# VM3300_V0_1.net
KiCad netlist of a schematic drawn in Altium Designer
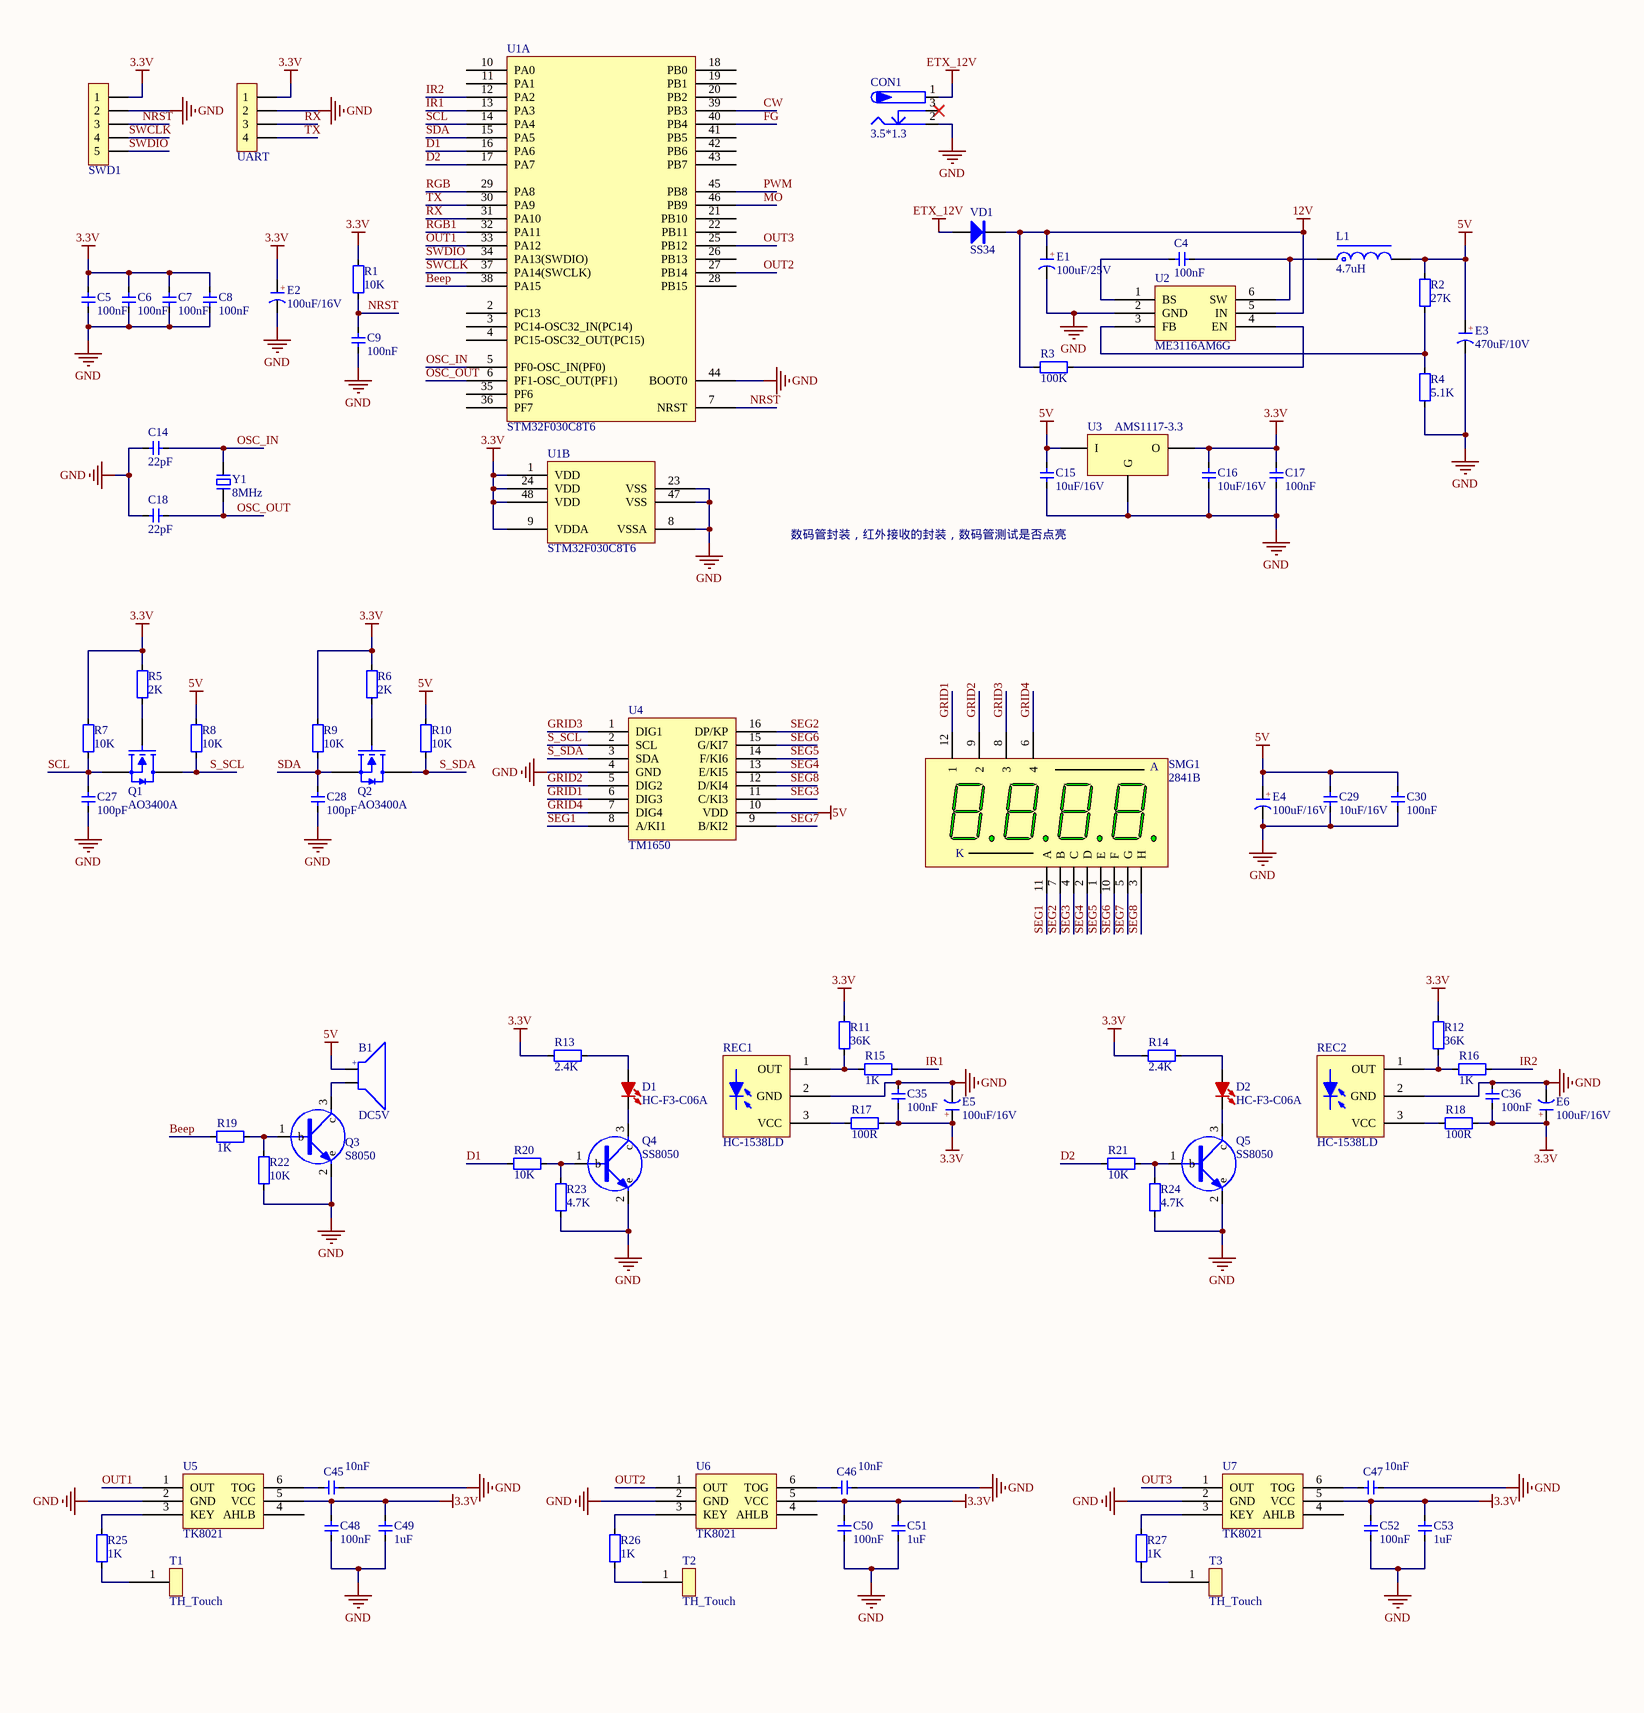
[diagram p0: VM3300_V0.1.SchDoc, left]
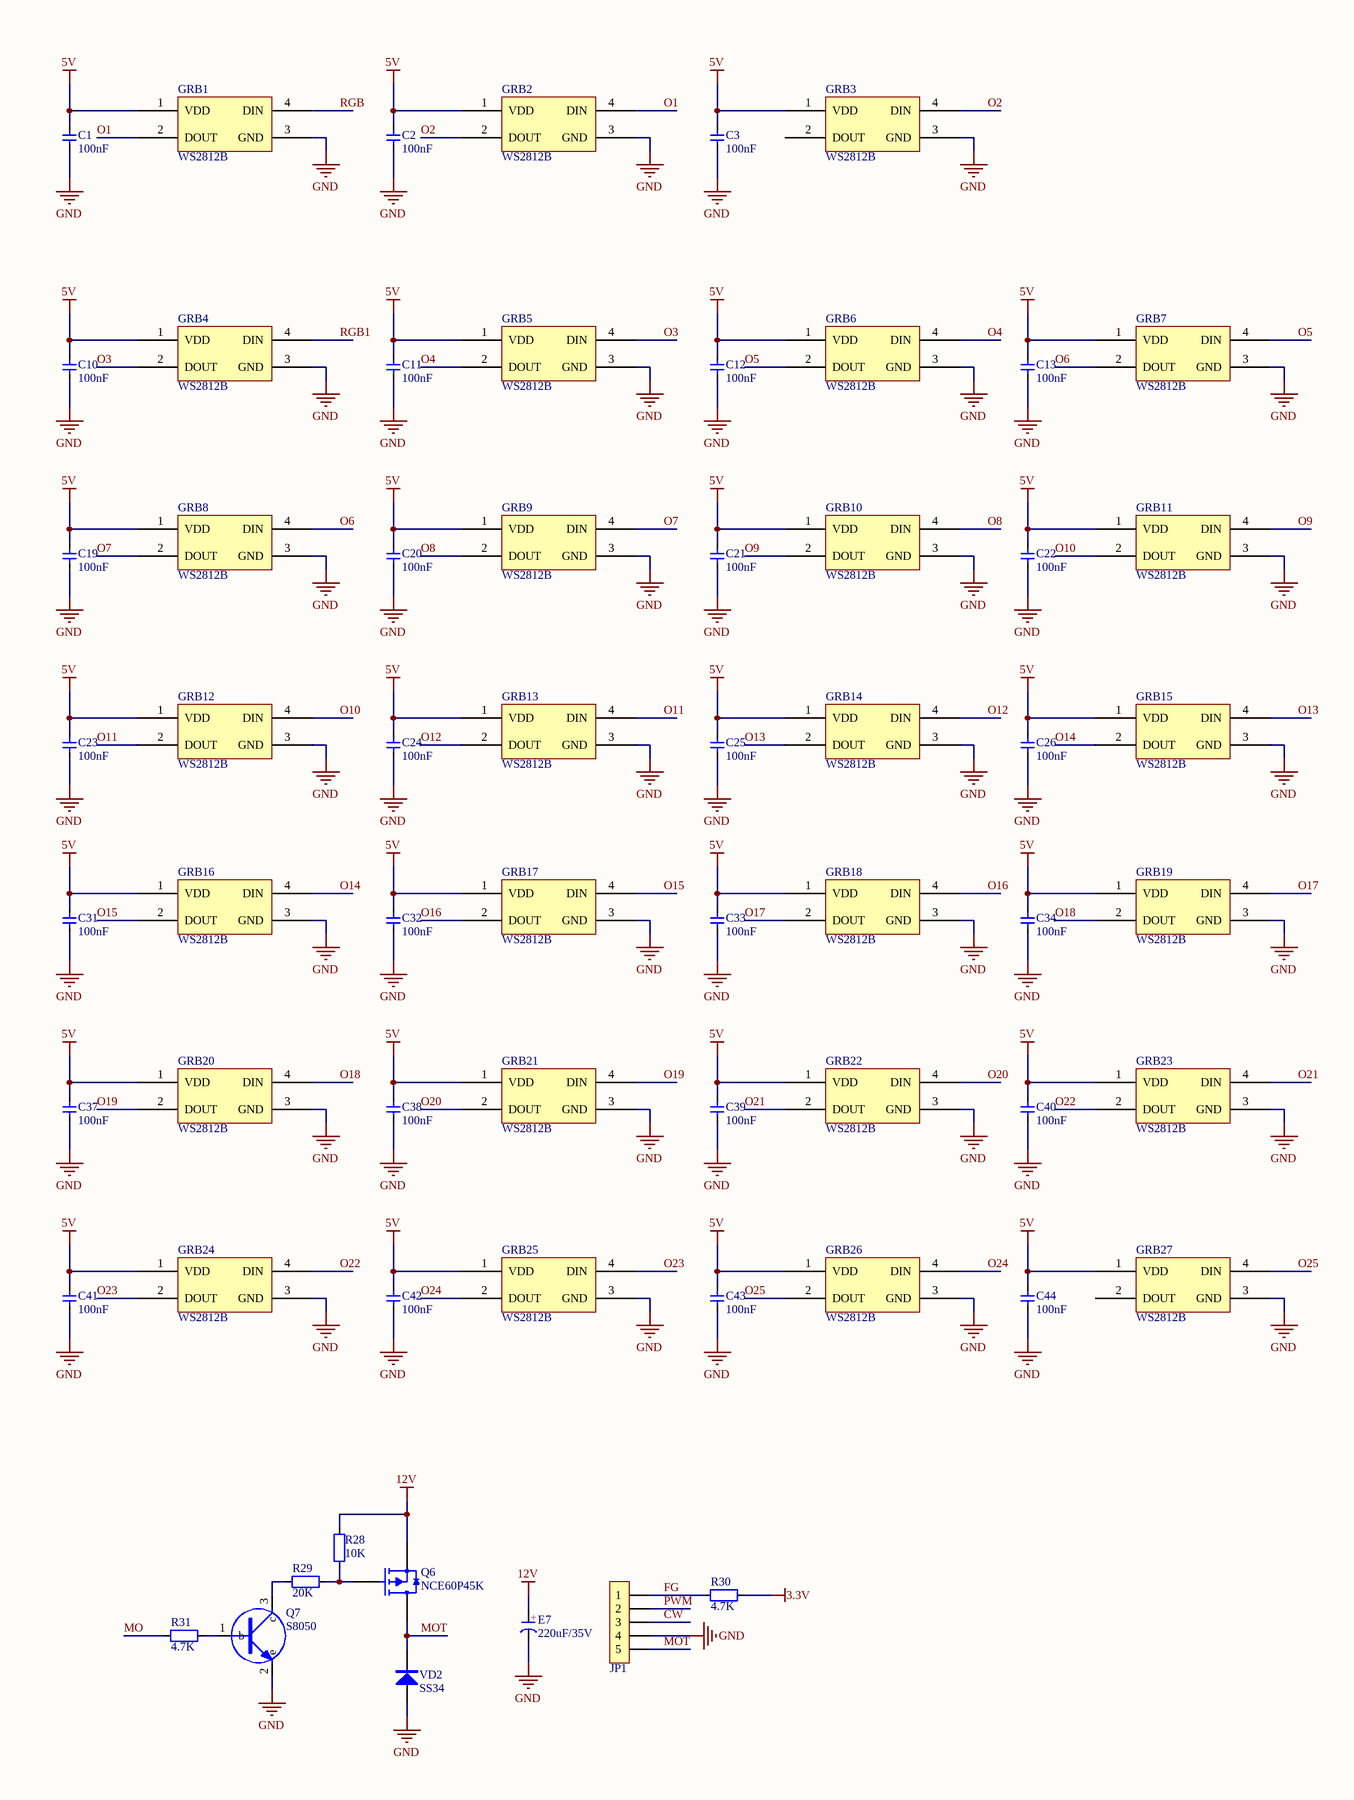
[diagram p1: VM3300_V0.1.SchDoc, right]

(export (version "E")
  (design (tool "Eeschema 10.0.6"))
  (components
    (comp (ref "B1")
      (value "DC5V")
      (footprint "BEEP 7.6x12x7.5")
      (description "蜂鸣器")
      (fields (field (name "版权归属") "源创客"))
      (libsource (lib "模块器件") (part "BEEP"))
    )
    (comp (ref "C1")
      (value "100nF")
      (footprint "C 0603")
      (description "无极性贴片电容")
      (fields (field (name "版权归属") "源创客"))
      (libsource (lib "电容") (part "C"))
    )
    (comp (ref "C2")
      (value "100nF")
      (footprint "C 0603")
      (description "无极性贴片电容")
      (fields (field (name "版权归属") "源创客"))
      (libsource (lib "电容") (part "C"))
    )
    (comp (ref "C3")
      (value "100nF")
      (footprint "C 0603")
      (description "无极性贴片电容")
      (fields (field (name "版权归属") "源创客"))
      (libsource (lib "电容") (part "C"))
    )
    (comp (ref "C4")
      (value "100nF")
      (footprint "C 0603")
      (description "无极性贴片电容")
      (fields (field (name "版权归属") "源创客"))
      (libsource (lib "电容") (part "C"))
    )
    (comp (ref "C5")
      (value "100nF")
      (footprint "C 0603")
      (description "无极性贴片电容")
      (fields (field (name "版权归属") "源创客"))
      (libsource (lib "电容") (part "C"))
    )
    (comp (ref "C6")
      (value "100nF")
      (footprint "C 0603")
      (description "无极性贴片电容")
      (fields (field (name "版权归属") "源创客"))
      (libsource (lib "电容") (part "C"))
    )
    (comp (ref "C7")
      (value "100nF")
      (footprint "C 0603")
      (description "无极性贴片电容")
      (fields (field (name "版权归属") "源创客"))
      (libsource (lib "电容") (part "C"))
    )
    (comp (ref "C8")
      (value "100nF")
      (footprint "C 0603")
      (description "无极性贴片电容")
      (fields (field (name "版权归属") "源创客"))
      (libsource (lib "电容") (part "C"))
    )
    (comp (ref "C9")
      (value "100nF")
      (footprint "C 0603")
      (description "无极性贴片电容")
      (fields (field (name "版权归属") "源创客"))
      (libsource (lib "电容") (part "C"))
    )
    (comp (ref "C10")
      (value "100nF")
      (footprint "C 0603")
      (description "无极性贴片电容")
      (fields (field (name "版权归属") "源创客"))
      (libsource (lib "电容") (part "C"))
    )
    (comp (ref "C11")
      (value "100nF")
      (footprint "C 0603")
      (description "无极性贴片电容")
      (fields (field (name "版权归属") "源创客"))
      (libsource (lib "电容") (part "C"))
    )
    (comp (ref "C12")
      (value "100nF")
      (footprint "C 0603")
      (description "无极性贴片电容")
      (fields (field (name "版权归属") "源创客"))
      (libsource (lib "电容") (part "C"))
    )
    (comp (ref "C13")
      (value "100nF")
      (footprint "C 0603")
      (description "无极性贴片电容")
      (fields (field (name "版权归属") "源创客"))
      (libsource (lib "电容") (part "C"))
    )
    (comp (ref "C14")
      (value "22pF")
      (footprint "C 0603")
      (description "无极性贴片电容")
      (fields (field (name "版权归属") "源创客"))
      (libsource (lib "电容") (part "C"))
    )
    (comp (ref "C15")
      (value "10uF/16V")
      (footprint "C 0805")
      (description "无极性贴片电容")
      (fields (field (name "版权归属") "源创客"))
      (libsource (lib "电容") (part "C"))
    )
    (comp (ref "C16")
      (value "10uF/16V")
      (footprint "C 0805")
      (description "无极性贴片电容")
      (fields (field (name "版权归属") "源创客"))
      (libsource (lib "电容") (part "C"))
    )
    (comp (ref "C17")
      (value "100nF")
      (footprint "C 0603")
      (description "无极性贴片电容")
      (fields (field (name "版权归属") "源创客"))
      (libsource (lib "电容") (part "C"))
    )
    (comp (ref "C18")
      (value "22pF")
      (footprint "C 0603")
      (description "无极性贴片电容")
      (fields (field (name "版权归属") "源创客"))
      (libsource (lib "电容") (part "C"))
    )
    (comp (ref "C19")
      (value "100nF")
      (footprint "C 0603")
      (description "无极性贴片电容")
      (fields (field (name "版权归属") "源创客"))
      (libsource (lib "电容") (part "C"))
    )
    (comp (ref "C20")
      (value "100nF")
      (footprint "C 0603")
      (description "无极性贴片电容")
      (fields (field (name "版权归属") "源创客"))
      (libsource (lib "电容") (part "C"))
    )
    (comp (ref "C21")
      (value "100nF")
      (footprint "C 0603")
      (description "无极性贴片电容")
      (fields (field (name "版权归属") "源创客"))
      (libsource (lib "电容") (part "C"))
    )
    (comp (ref "C22")
      (value "100nF")
      (footprint "C 0603")
      (description "无极性贴片电容")
      (fields (field (name "版权归属") "源创客"))
      (libsource (lib "电容") (part "C"))
    )
    (comp (ref "C23")
      (value "100nF")
      (footprint "C 0603")
      (description "无极性贴片电容")
      (fields (field (name "版权归属") "源创客"))
      (libsource (lib "电容") (part "C"))
    )
    (comp (ref "C24")
      (value "100nF")
      (footprint "C 0603")
      (description "无极性贴片电容")
      (fields (field (name "版权归属") "源创客"))
      (libsource (lib "电容") (part "C"))
    )
    (comp (ref "C25")
      (value "100nF")
      (footprint "C 0603")
      (description "无极性贴片电容")
      (fields (field (name "版权归属") "源创客"))
      (libsource (lib "电容") (part "C"))
    )
    (comp (ref "C26")
      (value "100nF")
      (footprint "C 0603")
      (description "无极性贴片电容")
      (fields (field (name "版权归属") "源创客"))
      (libsource (lib "电容") (part "C"))
    )
    (comp (ref "C27")
      (value "100pF")
      (footprint "C 0603")
      (description "无极性贴片电容")
      (fields (field (name "版权归属") "源创客"))
      (libsource (lib "电容") (part "C"))
    )
    (comp (ref "C28")
      (value "100pF")
      (footprint "C 0603")
      (description "无极性贴片电容")
      (fields (field (name "版权归属") "源创客"))
      (libsource (lib "电容") (part "C"))
    )
    (comp (ref "C29")
      (value "10uF/16V")
      (footprint "C 0805")
      (description "无极性贴片电容")
      (fields (field (name "版权归属") "源创客"))
      (libsource (lib "电容") (part "C"))
    )
    (comp (ref "C30")
      (value "100nF")
      (footprint "C 0603")
      (description "无极性贴片电容")
      (fields (field (name "版权归属") "源创客"))
      (libsource (lib "电容") (part "C"))
    )
    (comp (ref "C31")
      (value "100nF")
      (footprint "C 0603")
      (description "无极性贴片电容")
      (fields (field (name "版权归属") "源创客"))
      (libsource (lib "电容") (part "C"))
    )
    (comp (ref "C32")
      (value "100nF")
      (footprint "C 0603")
      (description "无极性贴片电容")
      (fields (field (name "版权归属") "源创客"))
      (libsource (lib "电容") (part "C"))
    )
    (comp (ref "C33")
      (value "100nF")
      (footprint "C 0603")
      (description "无极性贴片电容")
      (fields (field (name "版权归属") "源创客"))
      (libsource (lib "电容") (part "C"))
    )
    (comp (ref "C34")
      (value "100nF")
      (footprint "C 0603")
      (description "无极性贴片电容")
      (fields (field (name "版权归属") "源创客"))
      (libsource (lib "电容") (part "C"))
    )
    (comp (ref "C35")
      (value "100nF")
      (footprint "C 0603")
      (description "无极性贴片电容")
      (fields (field (name "版权归属") "源创客"))
      (libsource (lib "电容") (part "C"))
    )
    (comp (ref "C36")
      (value "100nF")
      (footprint "C 0603")
      (description "无极性贴片电容")
      (fields (field (name "版权归属") "源创客"))
      (libsource (lib "电容") (part "C"))
    )
    (comp (ref "C37")
      (value "100nF")
      (footprint "C 0603")
      (description "无极性贴片电容")
      (fields (field (name "版权归属") "源创客"))
      (libsource (lib "电容") (part "C"))
    )
    (comp (ref "C38")
      (value "100nF")
      (footprint "C 0603")
      (description "无极性贴片电容")
      (fields (field (name "版权归属") "源创客"))
      (libsource (lib "电容") (part "C"))
    )
    (comp (ref "C39")
      (value "100nF")
      (footprint "C 0603")
      (description "无极性贴片电容")
      (fields (field (name "版权归属") "源创客"))
      (libsource (lib "电容") (part "C"))
    )
    (comp (ref "C40")
      (value "100nF")
      (footprint "C 0603")
      (description "无极性贴片电容")
      (fields (field (name "版权归属") "源创客"))
      (libsource (lib "电容") (part "C"))
    )
    (comp (ref "C41")
      (value "100nF")
      (footprint "C 0603")
      (description "无极性贴片电容")
      (fields (field (name "版权归属") "源创客"))
      (libsource (lib "电容") (part "C"))
    )
    (comp (ref "C42")
      (value "100nF")
      (footprint "C 0603")
      (description "无极性贴片电容")
      (fields (field (name "版权归属") "源创客"))
      (libsource (lib "电容") (part "C"))
    )
    (comp (ref "C43")
      (value "100nF")
      (footprint "C 0603")
      (description "无极性贴片电容")
      (fields (field (name "版权归属") "源创客"))
      (libsource (lib "电容") (part "C"))
    )
    (comp (ref "C44")
      (value "100nF")
      (footprint "C 0603")
      (description "无极性贴片电容")
      (fields (field (name "版权归属") "源创客"))
      (libsource (lib "电容") (part "C"))
    )
    (comp (ref "C45")
      (value "10nF")
      (footprint "C 0603")
      (description "无极性贴片电容")
      (fields (field (name "版权归属") "源创客"))
      (libsource (lib "电容") (part "C"))
    )
    (comp (ref "C46")
      (value "10nF")
      (footprint "C 0603")
      (description "无极性贴片电容")
      (fields (field (name "版权归属") "源创客"))
      (libsource (lib "电容") (part "C"))
    )
    (comp (ref "C47")
      (value "10nF")
      (footprint "C 0603")
      (description "无极性贴片电容")
      (fields (field (name "版权归属") "源创客"))
      (libsource (lib "电容") (part "C"))
    )
    (comp (ref "C48")
      (value "100nF")
      (footprint "C 0603")
      (description "无极性贴片电容")
      (fields (field (name "版权归属") "源创客"))
      (libsource (lib "电容") (part "C"))
    )
    (comp (ref "C49")
      (value "1uF")
      (footprint "C 0603")
      (description "无极性贴片电容")
      (fields (field (name "版权归属") "源创客"))
      (libsource (lib "电容") (part "C"))
    )
    (comp (ref "C50")
      (value "100nF")
      (footprint "C 0603")
      (description "无极性贴片电容")
      (fields (field (name "版权归属") "源创客"))
      (libsource (lib "电容") (part "C"))
    )
    (comp (ref "C51")
      (value "1uF")
      (footprint "C 0603")
      (description "无极性贴片电容")
      (fields (field (name "版权归属") "源创客"))
      (libsource (lib "电容") (part "C"))
    )
    (comp (ref "C52")
      (value "100nF")
      (footprint "C 0603")
      (description "无极性贴片电容")
      (fields (field (name "版权归属") "源创客"))
      (libsource (lib "电容") (part "C"))
    )
    (comp (ref "C53")
      (value "1uF")
      (footprint "C 0603")
      (description "无极性贴片电容")
      (fields (field (name "版权归属") "源创客"))
      (libsource (lib "电容") (part "C"))
    )
    (comp (ref "CON1")
      (value "3.5*1.3")
      (footprint "DC-005")
      (description "低压电源接口")
      (fields (field (name "版权归属") "源创客"))
      (libsource (lib "接口类") (part "P-DC"))
    )
    (comp (ref "D1")
      (value "HC-F3-C06A")
      (footprint "HC-F3-C06A")
      (description "红外发射管")
      (libsource (lib "传感器") (part "HC-F3-C06A"))
    )
    (comp (ref "D2")
      (value "HC-F3-C06A")
      (footprint "HC-F3-C06A")
      (description "红外发射管")
      (libsource (lib "传感器") (part "HC-F3-C06A"))
    )
    (comp (ref "E1")
      (value "100uF/25V")
      (footprint "CAP 2.0*5*11 - BK")
      (description "直插电解电容")
      (fields (field (name "版权归属") "源创客"))
      (libsource (lib "电容") (part "C-CAP"))
    )
    (comp (ref "E2")
      (value "100uF/16V")
      (footprint "CAP 2.0*5*11 - BK")
      (description "直插电解电容")
      (fields (field (name "版权归属") "源创客"))
      (libsource (lib "电容") (part "C-CAP"))
    )
    (comp (ref "E3")
      (value "470uF/10V")
      (footprint "CAP 2.5*6.3*11.2 - BK")
      (description "直插电解电容")
      (fields (field (name "版权归属") "源创客"))
      (libsource (lib "电容") (part "C-CAP"))
    )
    (comp (ref "E4")
      (value "100uF/16V")
      (footprint "CAP 2.0*5*11 - BK")
      (description "直插电解电容")
      (fields (field (name "版权归属") "源创客"))
      (libsource (lib "电容") (part "C-CAP"))
    )
    (comp (ref "E5")
      (value "100uF/16V")
      (footprint "CAP 2.0*5*11 - BK")
      (description "直插电解电容")
      (fields (field (name "版权归属") "源创客"))
      (libsource (lib "电容") (part "C-CAP"))
    )
    (comp (ref "E6")
      (value "100uF/16V")
      (footprint "CAP 2.0*5*11 - BK")
      (description "直插电解电容")
      (fields (field (name "版权归属") "源创客"))
      (libsource (lib "电容") (part "C-CAP"))
    )
    (comp (ref "E7")
      (value "220uF/35V")
      (footprint "CAP 3.5*8*11.5 - BK")
      (description "直插电解电容")
      (fields (field (name "版权归属") "源创客"))
      (libsource (lib "电容") (part "C-CAP"))
    )
    (comp (ref "GRB1") (value "WS2812B") (footprint "WS2812B-3528") (libsource (lib "LED") (part "WS2812B")))
    (comp (ref "GRB2") (value "WS2812B") (footprint "WS2812B-3528") (libsource (lib "LED") (part "WS2812B")))
    (comp (ref "GRB3") (value "WS2812B") (footprint "WS2812B-3528") (libsource (lib "LED") (part "WS2812B")))
    (comp (ref "GRB4") (value "WS2812B") (footprint "WS2812B-3528") (libsource (lib "LED") (part "WS2812B")))
    (comp (ref "GRB5") (value "WS2812B") (footprint "WS2812B-3528") (libsource (lib "LED") (part "WS2812B")))
    (comp (ref "GRB6") (value "WS2812B") (footprint "WS2812B-3528") (libsource (lib "LED") (part "WS2812B")))
    (comp (ref "GRB7") (value "WS2812B") (footprint "WS2812B-3528") (libsource (lib "LED") (part "WS2812B")))
    (comp (ref "GRB8") (value "WS2812B") (footprint "WS2812B-3528") (libsource (lib "LED") (part "WS2812B")))
    (comp (ref "GRB9") (value "WS2812B") (footprint "WS2812B-3528") (libsource (lib "LED") (part "WS2812B")))
    (comp (ref "GRB10") (value "WS2812B") (footprint "WS2812B-3528") (libsource (lib "LED") (part "WS2812B")))
    (comp (ref "GRB11") (value "WS2812B") (footprint "WS2812B-3528") (libsource (lib "LED") (part "WS2812B")))
    (comp (ref "GRB12") (value "WS2812B") (footprint "WS2812B-3528") (libsource (lib "LED") (part "WS2812B")))
    (comp (ref "GRB13") (value "WS2812B") (footprint "WS2812B-3528") (libsource (lib "LED") (part "WS2812B")))
    (comp (ref "GRB14") (value "WS2812B") (footprint "WS2812B-3528") (libsource (lib "LED") (part "WS2812B")))
    (comp (ref "GRB15") (value "WS2812B") (footprint "WS2812B-3528") (libsource (lib "LED") (part "WS2812B")))
    (comp (ref "GRB16") (value "WS2812B") (footprint "WS2812B-3528") (libsource (lib "LED") (part "WS2812B")))
    (comp (ref "GRB17") (value "WS2812B") (footprint "WS2812B-3528") (libsource (lib "LED") (part "WS2812B")))
    (comp (ref "GRB18") (value "WS2812B") (footprint "WS2812B-3528") (libsource (lib "LED") (part "WS2812B")))
    (comp (ref "GRB19") (value "WS2812B") (footprint "WS2812B-3528") (libsource (lib "LED") (part "WS2812B")))
    (comp (ref "GRB20") (value "WS2812B") (footprint "WS2812B-3528") (libsource (lib "LED") (part "WS2812B")))
    (comp (ref "GRB21") (value "WS2812B") (footprint "WS2812B-3528") (libsource (lib "LED") (part "WS2812B")))
    (comp (ref "GRB22") (value "WS2812B") (footprint "WS2812B-3528") (libsource (lib "LED") (part "WS2812B")))
    (comp (ref "GRB23") (value "WS2812B") (footprint "WS2812B-3528") (libsource (lib "LED") (part "WS2812B")))
    (comp (ref "GRB24") (value "WS2812B") (footprint "WS2812B-3528") (libsource (lib "LED") (part "WS2812B")))
    (comp (ref "GRB25") (value "WS2812B") (footprint "WS2812B-3528") (libsource (lib "LED") (part "WS2812B")))
    (comp (ref "GRB26") (value "WS2812B") (footprint "WS2812B-3528") (libsource (lib "LED") (part "WS2812B")))
    (comp (ref "GRB27") (value "WS2812B") (footprint "WS2812B-3528") (libsource (lib "LED") (part "WS2812B")))
    (comp (ref "JP1")
      (value "HDR-1X5")
      (footprint "XH2.54-5P")
      (description "5P接插件")
      (fields (field (name "版权归属") "源创客"))
      (libsource (lib "排针-排母") (part "Header 5"))
    )
    (comp (ref "L1")
      (value "4.7uH")
      (footprint "CD32")
      (description "贴片功率电感")
      (fields (field (name "版权归属") "源创客"))
      (libsource (lib "电感") (part "L-CD"))
    )
    (comp (ref "Q1")
      (value "AO3400A")
      (footprint "SOT23-3")
      (description "N-MOS")
      (libsource (lib "三极管") (part "AO3400A"))
    )
    (comp (ref "Q2")
      (value "AO3400A")
      (footprint "SOT23-3")
      (description "N-MOS")
      (libsource (lib "三极管") (part "AO3400A"))
    )
    (comp (ref "Q3") (value "S8050") (footprint "SOT23-3L") (libsource (lib "三极管") (part "NPN")))
    (comp (ref "Q4") (value "SS8050") (footprint "SOT23-3L") (libsource (lib "三极管") (part "NPN")))
    (comp (ref "Q5") (value "SS8050") (footprint "SOT23-3L") (libsource (lib "三极管") (part "NPN")))
    (comp (ref "Q6")
      (value "NCE60P45K")
      (footprint "NCE_MOS")
      (description "NCE系类的MOS")
      (libsource (lib "三极管") (part "NCE_MOS"))
    )
    (comp (ref "Q7") (value "S8050") (footprint "SOT23-3L") (libsource (lib "三极管") (part "NPN")))
    (comp (ref "R1")
      (value "10K")
      (footprint "R 0603")
      (description "贴片电阻")
      (fields (field (name "版权归属") "源创客"))
      (libsource (lib "") (part "R_1"))
    )
    (comp (ref "R2")
      (value "27K")
      (footprint "R 0603")
      (description "贴片电阻")
      (fields (field (name "版权归属") "源创客"))
      (libsource (lib "") (part "R_1"))
    )
    (comp (ref "R3")
      (value "100K")
      (footprint "R 0603")
      (description "贴片电阻")
      (fields (field (name "版权归属") "源创客"))
      (libsource (lib "电阻") (part "R"))
    )
    (comp (ref "R4")
      (value "5.1K")
      (footprint "R 0603")
      (description "贴片电阻")
      (fields (field (name "版权归属") "源创客"))
      (libsource (lib "") (part "R_1"))
    )
    (comp (ref "R5")
      (value "2K")
      (footprint "R 0603")
      (description "贴片电阻")
      (fields (field (name "版权归属") "源创客"))
      (libsource (lib "") (part "R_1"))
    )
    (comp (ref "R6")
      (value "2K")
      (footprint "R 0603")
      (description "贴片电阻")
      (fields (field (name "版权归属") "源创客"))
      (libsource (lib "") (part "R_1"))
    )
    (comp (ref "R7")
      (value "10K")
      (footprint "R 0603")
      (description "贴片电阻")
      (fields (field (name "版权归属") "源创客"))
      (libsource (lib "") (part "R_1"))
    )
    (comp (ref "R8")
      (value "10K")
      (footprint "R 0603")
      (description "贴片电阻")
      (fields (field (name "版权归属") "源创客"))
      (libsource (lib "") (part "R_1"))
    )
    (comp (ref "R9")
      (value "10K")
      (footprint "R 0603")
      (description "贴片电阻")
      (fields (field (name "版权归属") "源创客"))
      (libsource (lib "") (part "R_1"))
    )
    (comp (ref "R10")
      (value "10K")
      (footprint "R 0603")
      (description "贴片电阻")
      (fields (field (name "版权归属") "源创客"))
      (libsource (lib "") (part "R_1"))
    )
    (comp (ref "R11")
      (value "36K")
      (footprint "R 0603")
      (description "贴片电阻")
      (fields (field (name "版权归属") "源创客"))
      (libsource (lib "") (part "R_1"))
    )
    (comp (ref "R12")
      (value "36K")
      (footprint "R 0603")
      (description "贴片电阻")
      (fields (field (name "版权归属") "源创客"))
      (libsource (lib "") (part "R_1"))
    )
    (comp (ref "R13")
      (value "2.4K")
      (footprint "R 0603")
      (description "贴片电阻")
      (fields (field (name "版权归属") "源创客"))
      (libsource (lib "电阻") (part "R"))
    )
    (comp (ref "R14")
      (value "2.4K")
      (footprint "R 0603")
      (description "贴片电阻")
      (fields (field (name "版权归属") "源创客"))
      (libsource (lib "电阻") (part "R"))
    )
    (comp (ref "R15")
      (value "1K")
      (footprint "R 0603")
      (description "贴片电阻")
      (fields (field (name "版权归属") "源创客"))
      (libsource (lib "电阻") (part "R"))
    )
    (comp (ref "R16")
      (value "1K")
      (footprint "R 0603")
      (description "贴片电阻")
      (fields (field (name "版权归属") "源创客"))
      (libsource (lib "电阻") (part "R"))
    )
    (comp (ref "R17")
      (value "100R")
      (footprint "R 0603")
      (description "贴片电阻")
      (fields (field (name "版权归属") "源创客"))
      (libsource (lib "电阻") (part "R"))
    )
    (comp (ref "R18")
      (value "100R")
      (footprint "R 0603")
      (description "贴片电阻")
      (fields (field (name "版权归属") "源创客"))
      (libsource (lib "电阻") (part "R"))
    )
    (comp (ref "R19")
      (value "1K")
      (footprint "R 0603")
      (description "贴片电阻")
      (fields (field (name "版权归属") "源创客"))
      (libsource (lib "电阻") (part "R"))
    )
    (comp (ref "R20")
      (value "10K")
      (footprint "R 0603")
      (description "贴片电阻")
      (fields (field (name "版权归属") "源创客"))
      (libsource (lib "电阻") (part "R"))
    )
    (comp (ref "R21")
      (value "10K")
      (footprint "R 0603")
      (description "贴片电阻")
      (fields (field (name "版权归属") "源创客"))
      (libsource (lib "电阻") (part "R"))
    )
    (comp (ref "R22")
      (value "10K")
      (footprint "R 0603")
      (description "贴片电阻")
      (fields (field (name "版权归属") "源创客"))
      (libsource (lib "") (part "R_1"))
    )
    (comp (ref "R23")
      (value "4.7K")
      (footprint "R 0603")
      (description "贴片电阻")
      (fields (field (name "版权归属") "源创客"))
      (libsource (lib "") (part "R_1"))
    )
    (comp (ref "R24")
      (value "4.7K")
      (footprint "R 0603")
      (description "贴片电阻")
      (fields (field (name "版权归属") "源创客"))
      (libsource (lib "") (part "R_1"))
    )
    (comp (ref "R25")
      (value "1K")
      (footprint "R 0603")
      (description "贴片电阻")
      (fields (field (name "版权归属") "源创客"))
      (libsource (lib "") (part "R_1"))
    )
    (comp (ref "R26")
      (value "1K")
      (footprint "R 0603")
      (description "贴片电阻")
      (fields (field (name "版权归属") "源创客"))
      (libsource (lib "") (part "R_1"))
    )
    (comp (ref "R27")
      (value "1K")
      (footprint "R 0603")
      (description "贴片电阻")
      (fields (field (name "版权归属") "源创客"))
      (libsource (lib "") (part "R_1"))
    )
    (comp (ref "R28")
      (value "10K")
      (footprint "R 0603")
      (description "贴片电阻")
      (fields (field (name "版权归属") "源创客"))
      (libsource (lib "") (part "R_1"))
    )
    (comp (ref "R29")
      (value "20K")
      (footprint "R 0603")
      (description "贴片电阻")
      (fields (field (name "版权归属") "源创客"))
      (libsource (lib "电阻") (part "R"))
    )
    (comp (ref "R30")
      (value "4.7K")
      (footprint "R 0603")
      (description "贴片电阻")
      (fields (field (name "版权归属") "源创客"))
      (libsource (lib "电阻") (part "R"))
    )
    (comp (ref "R31")
      (value "4.7K")
      (footprint "R 0603")
      (description "贴片电阻")
      (fields (field (name "版权归属") "源创客"))
      (libsource (lib "电阻") (part "R"))
    )
    (comp (ref "REC1")
      (value "HC-1538LD")
      (footprint "HC-1538LD")
      (description "红外接收管")
      (libsource (lib "传感器") (part "HC-1538LD"))
    )
    (comp (ref "REC2")
      (value "HC-1538LD")
      (footprint "HC-1538LD")
      (description "红外接收管")
      (libsource (lib "传感器") (part "HC-1538LD"))
    )
    (comp (ref "SMG1")
      (value "2841B")
      (footprint "SMG 0.28-4P_B")
      (description "0.28寸4位共阳数码管")
      (fields (field (name "版权归属") "源创客"))
      (libsource (lib "显示器件") (part "2841B"))
    )
    (comp (ref "SWD1")
      (value "HDR-1X5")
      (footprint "SWD_JOANLAB")
      (description "5P接插件")
      (fields (field (name "版权归属") "源创客"))
      (libsource (lib "排针-排母") (part "Header 5"))
    )
    (comp (ref "T1")
      (value "TH_Touch")
      (footprint "TH_Touch")
      (description "触摸弹簧，用于触摸感应")
      (libsource (lib "模块器件") (part "TH_Touch"))
    )
    (comp (ref "T2")
      (value "TH_Touch")
      (footprint "TH_Touch")
      (description "触摸弹簧，用于触摸感应")
      (libsource (lib "模块器件") (part "TH_Touch"))
    )
    (comp (ref "T3")
      (value "TH_Touch")
      (footprint "TH_Touch")
      (description "触摸弹簧，用于触摸感应")
      (libsource (lib "模块器件") (part "TH_Touch"))
    )
    (comp (ref "U1")
      (value "STM32F030C8T6")
      (footprint "STM32F030C8T6")
      (libsource (lib "STM32系列单片机") (part "STM32F030C8T6"))
    )
    (comp (ref "U2")
      (value "ME3116AM6G")
      (footprint "ME3116AM6G")
      (description "DC-DC电源芯片  24-40V->5V")
      (libsource (lib "变压器") (part "ME3116AM6G"))
    )
    (comp (ref "U3")
      (value "AMS1117-3.3")
      (footprint "AMS1117-3.3")
      (description "转3.3V电压")
      (libsource (lib "变压器") (part "AMS1117-3.3"))
    )
    (comp (ref "U4")
      (value "TM1650")
      (footprint "TM1650")
      (description "TM1650是一种带键盘扫描接口的LED（发光二极管显示器）驱动控制专用IC,内部集成有MCU\r\n数字接口、数据锁存器、LED驱动、键盘扫描等电路。")
      (libsource (lib "显示芯片") (part "TM1650"))
    )
    (comp (ref "U5")
      (value "TK8021")
      (footprint "TK8021")
      (description "单通道自校正触摸感应芯片")
      (libsource (lib "常用芯片") (part "TTP2233"))
    )
    (comp (ref "U6")
      (value "TK8021")
      (footprint "TK8021")
      (description "单通道自校正触摸感应芯片")
      (libsource (lib "常用芯片") (part "TTP2233"))
    )
    (comp (ref "U7")
      (value "TK8021")
      (footprint "TK8021")
      (description "单通道自校正触摸感应芯片")
      (libsource (lib "常用芯片") (part "TTP2233"))
    )
    (comp (ref "UART")
      (value "HDR-1X4")
      (footprint "XH2.54-4P")
      (description "4P接插件")
      (fields (field (name "版权归属") "源创客"))
      (libsource (lib "排针-排母") (part "Header 4"))
    )
    (comp (ref "VD1")
      (value "SS34")
      (footprint "SMA")
      (description "肖特基二极管")
      (fields (field (name "版权归属") "源创客"))
      (libsource (lib "二极管-整流桥") (part "SS34"))
    )
    (comp (ref "VD2")
      (value "SS34")
      (footprint "SMA")
      (description "肖特基二极管")
      (fields (field (name "版权归属") "源创客"))
      (libsource (lib "二极管-整流桥") (part "SS34"))
    )
    (comp (ref "Y1")
      (value "8MHz")
      (footprint "XTAL-49S SMD")
      (description "2脚晶振")
      (fields (field (name "版权归属") "源创客"))
      (libsource (lib "晶振") (part "XTAL-2"))
    )
  )
  (nets
    (net (code "1") (name "/Beep") (class "Default")
      (node (ref "R19") (pin "1") (pinfunction "1_1") (pintype "passive"))
      (node (ref "U1") (pin "38") (pinfunction "PA15_38") (pintype "passive"))
    )
    (net (code "2") (name "/CW") (class "Default")
      (node (ref "JP1") (pin "3") (pinfunction "3_3") (pintype "passive"))
      (node (ref "U1") (pin "39") (pinfunction "PB3_39") (pintype "passive"))
    )
    (net (code "3") (name "/D1") (class "Default")
      (node (ref "R20") (pin "1") (pinfunction "1_1") (pintype "passive"))
      (node (ref "U1") (pin "16") (pinfunction "PA6_16") (pintype "passive"))
    )
    (net (code "4") (name "/D2") (class "Default")
      (node (ref "R21") (pin "1") (pinfunction "1_1") (pintype "passive"))
      (node (ref "U1") (pin "17") (pinfunction "PA7_17") (pintype "passive"))
    )
    (net (code "5") (name "/FG") (class "Default")
      (node (ref "JP1") (pin "1") (pinfunction "1_1") (pintype "passive"))
      (node (ref "R30") (pin "1") (pinfunction "1_1") (pintype "passive"))
      (node (ref "U1") (pin "40") (pinfunction "PB4_40") (pintype "passive"))
    )
    (net (code "6") (name "/GRID1") (class "Default")
      (node (ref "SMG1") (pin "12") (pinfunction "1_12") (pintype "passive"))
      (node (ref "U4") (pin "6") (pinfunction "DIG3_6") (pintype "passive"))
    )
    (net (code "7") (name "/GRID2") (class "Default")
      (node (ref "SMG1") (pin "9") (pinfunction "2_9") (pintype "passive"))
      (node (ref "U4") (pin "5") (pinfunction "DIG2_5") (pintype "passive"))
    )
    (net (code "8") (name "/GRID3") (class "Default")
      (node (ref "SMG1") (pin "8") (pinfunction "3_8") (pintype "passive"))
      (node (ref "U4") (pin "1") (pinfunction "DIG1_1") (pintype "passive"))
    )
    (net (code "9") (name "/GRID4") (class "Default")
      (node (ref "SMG1") (pin "6") (pinfunction "4_6") (pintype "passive"))
      (node (ref "U4") (pin "7") (pinfunction "DIG4_7") (pintype "passive"))
    )
    (net (code "10") (name "/IR1") (class "Default")
      (node (ref "R15") (pin "2") (pinfunction "2_2") (pintype "passive"))
      (node (ref "U1") (pin "13") (pinfunction "PA3_13") (pintype "passive"))
    )
    (net (code "11") (name "/IR2") (class "Default")
      (node (ref "R16") (pin "2") (pinfunction "2_2") (pintype "passive"))
      (node (ref "U1") (pin "12") (pinfunction "PA2_12") (pintype "passive"))
    )
    (net (code "12") (name "/MO") (class "Default")
      (node (ref "R31") (pin "1") (pinfunction "1_1") (pintype "passive"))
      (node (ref "U1") (pin "46") (pinfunction "PB9_46") (pintype "passive"))
    )
    (net (code "13") (name "/MOT") (class "Default")
      (node (ref "JP1") (pin "5") (pinfunction "5_5") (pintype "passive"))
      (node (ref "Q6") (pin "2") (pinfunction "D_2") (pintype "passive"))
      (node (ref "VD2") (pin "2") (pinfunction "K_2") (pintype "passive"))
    )
    (net (code "14") (name "/NRST") (class "Default")
      (node (ref "C9") (pin "2") (pinfunction "2_2") (pintype "passive"))
      (node (ref "R1") (pin "1") (pinfunction "1_1") (pintype "passive"))
      (node (ref "SWD1") (pin "3") (pinfunction "3_3") (pintype "passive"))
      (node (ref "U1") (pin "7") (pinfunction "NRST_7") (pintype "passive"))
    )
    (net (code "15") (name "/O1") (class "Default")
      (node (ref "GRB1") (pin "2") (pinfunction "DOUT_2") (pintype "passive"))
      (node (ref "GRB2") (pin "4") (pinfunction "DIN_4") (pintype "passive"))
    )
    (net (code "16") (name "/O2") (class "Default")
      (node (ref "GRB2") (pin "2") (pinfunction "DOUT_2") (pintype "passive"))
      (node (ref "GRB3") (pin "4") (pinfunction "DIN_4") (pintype "passive"))
    )
    (net (code "17") (name "/O3") (class "Default")
      (node (ref "GRB4") (pin "2") (pinfunction "DOUT_2") (pintype "passive"))
      (node (ref "GRB5") (pin "4") (pinfunction "DIN_4") (pintype "passive"))
    )
    (net (code "18") (name "/O4") (class "Default")
      (node (ref "GRB5") (pin "2") (pinfunction "DOUT_2") (pintype "passive"))
      (node (ref "GRB6") (pin "4") (pinfunction "DIN_4") (pintype "passive"))
    )
    (net (code "19") (name "/O5") (class "Default")
      (node (ref "GRB6") (pin "2") (pinfunction "DOUT_2") (pintype "passive"))
      (node (ref "GRB7") (pin "4") (pinfunction "DIN_4") (pintype "passive"))
    )
    (net (code "20") (name "/O6") (class "Default")
      (node (ref "GRB7") (pin "2") (pinfunction "DOUT_2") (pintype "passive"))
      (node (ref "GRB8") (pin "4") (pinfunction "DIN_4") (pintype "passive"))
    )
    (net (code "21") (name "/O7") (class "Default")
      (node (ref "GRB8") (pin "2") (pinfunction "DOUT_2") (pintype "passive"))
      (node (ref "GRB9") (pin "4") (pinfunction "DIN_4") (pintype "passive"))
    )
    (net (code "22") (name "/O8") (class "Default")
      (node (ref "GRB10") (pin "4") (pinfunction "DIN_4") (pintype "passive"))
      (node (ref "GRB9") (pin "2") (pinfunction "DOUT_2") (pintype "passive"))
    )
    (net (code "23") (name "/O9") (class "Default")
      (node (ref "GRB10") (pin "2") (pinfunction "DOUT_2") (pintype "passive"))
      (node (ref "GRB11") (pin "4") (pinfunction "DIN_4") (pintype "passive"))
    )
    (net (code "24") (name "/O10") (class "Default")
      (node (ref "GRB11") (pin "2") (pinfunction "DOUT_2") (pintype "passive"))
      (node (ref "GRB12") (pin "4") (pinfunction "DIN_4") (pintype "passive"))
    )
    (net (code "25") (name "/O11") (class "Default")
      (node (ref "GRB12") (pin "2") (pinfunction "DOUT_2") (pintype "passive"))
      (node (ref "GRB13") (pin "4") (pinfunction "DIN_4") (pintype "passive"))
    )
    (net (code "26") (name "/O12") (class "Default")
      (node (ref "GRB13") (pin "2") (pinfunction "DOUT_2") (pintype "passive"))
      (node (ref "GRB14") (pin "4") (pinfunction "DIN_4") (pintype "passive"))
    )
    (net (code "27") (name "/O13") (class "Default")
      (node (ref "GRB14") (pin "2") (pinfunction "DOUT_2") (pintype "passive"))
      (node (ref "GRB15") (pin "4") (pinfunction "DIN_4") (pintype "passive"))
    )
    (net (code "28") (name "/O14") (class "Default")
      (node (ref "GRB15") (pin "2") (pinfunction "DOUT_2") (pintype "passive"))
      (node (ref "GRB16") (pin "4") (pinfunction "DIN_4") (pintype "passive"))
    )
    (net (code "29") (name "/O15") (class "Default")
      (node (ref "GRB16") (pin "2") (pinfunction "DOUT_2") (pintype "passive"))
      (node (ref "GRB17") (pin "4") (pinfunction "DIN_4") (pintype "passive"))
    )
    (net (code "30") (name "/O16") (class "Default")
      (node (ref "GRB17") (pin "2") (pinfunction "DOUT_2") (pintype "passive"))
      (node (ref "GRB18") (pin "4") (pinfunction "DIN_4") (pintype "passive"))
    )
    (net (code "31") (name "/O17") (class "Default")
      (node (ref "GRB18") (pin "2") (pinfunction "DOUT_2") (pintype "passive"))
      (node (ref "GRB19") (pin "4") (pinfunction "DIN_4") (pintype "passive"))
    )
    (net (code "32") (name "/O18") (class "Default")
      (node (ref "GRB19") (pin "2") (pinfunction "DOUT_2") (pintype "passive"))
      (node (ref "GRB20") (pin "4") (pinfunction "DIN_4") (pintype "passive"))
    )
    (net (code "33") (name "/O19") (class "Default")
      (node (ref "GRB20") (pin "2") (pinfunction "DOUT_2") (pintype "passive"))
      (node (ref "GRB21") (pin "4") (pinfunction "DIN_4") (pintype "passive"))
    )
    (net (code "34") (name "/O20") (class "Default")
      (node (ref "GRB21") (pin "2") (pinfunction "DOUT_2") (pintype "passive"))
      (node (ref "GRB22") (pin "4") (pinfunction "DIN_4") (pintype "passive"))
    )
    (net (code "35") (name "/O21") (class "Default")
      (node (ref "GRB22") (pin "2") (pinfunction "DOUT_2") (pintype "passive"))
      (node (ref "GRB23") (pin "4") (pinfunction "DIN_4") (pintype "passive"))
    )
    (net (code "36") (name "/O22") (class "Default")
      (node (ref "GRB23") (pin "2") (pinfunction "DOUT_2") (pintype "passive"))
      (node (ref "GRB24") (pin "4") (pinfunction "DIN_4") (pintype "passive"))
    )
    (net (code "37") (name "/O23") (class "Default")
      (node (ref "GRB24") (pin "2") (pinfunction "DOUT_2") (pintype "passive"))
      (node (ref "GRB25") (pin "4") (pinfunction "DIN_4") (pintype "passive"))
    )
    (net (code "38") (name "/O24") (class "Default")
      (node (ref "GRB25") (pin "2") (pinfunction "DOUT_2") (pintype "passive"))
      (node (ref "GRB26") (pin "4") (pinfunction "DIN_4") (pintype "passive"))
    )
    (net (code "39") (name "/O25") (class "Default")
      (node (ref "GRB26") (pin "2") (pinfunction "DOUT_2") (pintype "passive"))
      (node (ref "GRB27") (pin "4") (pinfunction "DIN_4") (pintype "passive"))
    )
    (net (code "40") (name "/OSC_IN") (class "Default")
      (node (ref "C14") (pin "2") (pinfunction "2_2") (pintype "passive"))
      (node (ref "U1") (pin "5") (pinfunction "PF0-OSC_IN(PF0)_5") (pintype "passive"))
      (node (ref "Y1") (pin "2") (pinfunction "2_2") (pintype "passive"))
    )
    (net (code "41") (name "/OSC_OUT") (class "Default")
      (node (ref "C18") (pin "2") (pinfunction "2_2") (pintype "passive"))
      (node (ref "U1") (pin "6") (pinfunction "PF1-OSC_OUT(PF1)_6") (pintype "passive"))
      (node (ref "Y1") (pin "1") (pinfunction "1_1") (pintype "passive"))
    )
    (net (code "42") (name "/OUT1") (class "Default")
      (node (ref "U1") (pin "33") (pinfunction "PA12_33") (pintype "passive"))
      (node (ref "U5") (pin "1") (pinfunction "OUT_1") (pintype "passive"))
    )
    (net (code "43") (name "/OUT2") (class "Default")
      (node (ref "U1") (pin "27") (pinfunction "PB14_27") (pintype "passive"))
      (node (ref "U6") (pin "1") (pinfunction "OUT_1") (pintype "passive"))
    )
    (net (code "44") (name "/OUT3") (class "Default")
      (node (ref "U1") (pin "25") (pinfunction "PB12_25") (pintype "passive"))
      (node (ref "U7") (pin "1") (pinfunction "OUT_1") (pintype "passive"))
    )
    (net (code "45") (name "/PWM") (class "Default")
      (node (ref "JP1") (pin "2") (pinfunction "2_2") (pintype "passive"))
      (node (ref "U1") (pin "45") (pinfunction "PB8_45") (pintype "passive"))
    )
    (net (code "46") (name "/RGB") (class "Default")
      (node (ref "GRB1") (pin "4") (pinfunction "DIN_4") (pintype "passive"))
      (node (ref "U1") (pin "29") (pinfunction "PA8_29") (pintype "passive"))
    )
    (net (code "47") (name "/RGB1") (class "Default")
      (node (ref "GRB4") (pin "4") (pinfunction "DIN_4") (pintype "passive"))
      (node (ref "U1") (pin "32") (pinfunction "PA11_32") (pintype "passive"))
    )
    (net (code "48") (name "/RX") (class "Default")
      (node (ref "U1") (pin "31") (pinfunction "PA10_31") (pintype "passive"))
      (node (ref "UART") (pin "3") (pinfunction "3_3") (pintype "passive"))
    )
    (net (code "49") (name "/SCL") (class "Default")
      (node (ref "C27") (pin "2") (pinfunction "2_2") (pintype "passive"))
      (node (ref "Q1") (pin "3") (pinfunction "S_3") (pintype "passive"))
      (node (ref "R7") (pin "1") (pinfunction "1_1") (pintype "passive"))
      (node (ref "U1") (pin "14") (pinfunction "PA4_14") (pintype "passive"))
    )
    (net (code "50") (name "/SDA") (class "Default")
      (node (ref "C28") (pin "2") (pinfunction "2_2") (pintype "passive"))
      (node (ref "Q2") (pin "3") (pinfunction "S_3") (pintype "passive"))
      (node (ref "R9") (pin "1") (pinfunction "1_1") (pintype "passive"))
      (node (ref "U1") (pin "15") (pinfunction "PA5_15") (pintype "passive"))
    )
    (net (code "51") (name "/SEG1") (class "Default")
      (node (ref "SMG1") (pin "11") (pinfunction "A_11") (pintype "passive"))
      (node (ref "U4") (pin "8") (pinfunction "A/KI1_8") (pintype "passive"))
    )
    (net (code "52") (name "/SEG2") (class "Default")
      (node (ref "SMG1") (pin "7") (pinfunction "B_7") (pintype "passive"))
      (node (ref "U4") (pin "16") (pinfunction "DP/KP_16") (pintype "passive"))
    )
    (net (code "53") (name "/SEG3") (class "Default")
      (node (ref "SMG1") (pin "4") (pinfunction "C_4") (pintype "passive"))
      (node (ref "U4") (pin "11") (pinfunction "C/KI3_11") (pintype "passive"))
    )
    (net (code "54") (name "/SEG4") (class "Default")
      (node (ref "SMG1") (pin "2") (pinfunction "D_2") (pintype "passive"))
      (node (ref "U4") (pin "13") (pinfunction "E/KI5_13") (pintype "passive"))
    )
    (net (code "55") (name "/SEG5") (class "Default")
      (node (ref "SMG1") (pin "1") (pinfunction "E_1") (pintype "passive"))
      (node (ref "U4") (pin "14") (pinfunction "F/KI6_14") (pintype "passive"))
    )
    (net (code "56") (name "/SEG6") (class "Default")
      (node (ref "SMG1") (pin "10") (pinfunction "F_10") (pintype "passive"))
      (node (ref "U4") (pin "15") (pinfunction "G/KI7_15") (pintype "passive"))
    )
    (net (code "57") (name "/SEG7") (class "Default")
      (node (ref "SMG1") (pin "5") (pinfunction "G_5") (pintype "passive"))
      (node (ref "U4") (pin "9") (pinfunction "B/KI2_9") (pintype "passive"))
    )
    (net (code "58") (name "/SEG8") (class "Default")
      (node (ref "SMG1") (pin "3") (pinfunction "H_3") (pintype "passive"))
      (node (ref "U4") (pin "12") (pinfunction "D/KI4_12") (pintype "passive"))
    )
    (net (code "59") (name "/SWCLK") (class "Default")
      (node (ref "SWD1") (pin "4") (pinfunction "4_4") (pintype "passive"))
      (node (ref "U1") (pin "37") (pinfunction "PA14(SWCLK)_37") (pintype "passive"))
    )
    (net (code "60") (name "/SWDIO") (class "Default")
      (node (ref "SWD1") (pin "5") (pinfunction "5_5") (pintype "passive"))
      (node (ref "U1") (pin "34") (pinfunction "PA13(SWDIO)_34") (pintype "passive"))
    )
    (net (code "61") (name "/S_SCL") (class "Default")
      (node (ref "Q1") (pin "2") (pinfunction "D_2") (pintype "passive"))
      (node (ref "R8") (pin "1") (pinfunction "1_1") (pintype "passive"))
      (node (ref "U4") (pin "2") (pinfunction "SCL_2") (pintype "passive"))
    )
    (net (code "62") (name "/S_SDA") (class "Default")
      (node (ref "Q2") (pin "2") (pinfunction "D_2") (pintype "passive"))
      (node (ref "R10") (pin "1") (pinfunction "1_1") (pintype "passive"))
      (node (ref "U4") (pin "3") (pinfunction "SDA_3") (pintype "passive"))
    )
    (net (code "63") (name "/TX") (class "Default")
      (node (ref "U1") (pin "30") (pinfunction "PA9_30") (pintype "passive"))
      (node (ref "UART") (pin "4") (pinfunction "4_4") (pintype "passive"))
    )
    (net (code "64") (name "3.3V") (class "Default")
      (node (ref "C16") (pin "2") (pinfunction "2_2") (pintype "passive"))
      (node (ref "C17") (pin "2") (pinfunction "2_2") (pintype "passive"))
      (node (ref "C35") (pin "1") (pinfunction "1_1") (pintype "passive"))
      (node (ref "C36") (pin "1") (pinfunction "1_1") (pintype "passive"))
      (node (ref "C48") (pin "2") (pinfunction "2_2") (pintype "passive"))
      (node (ref "C49") (pin "2") (pinfunction "2_2") (pintype "passive"))
      (node (ref "C5") (pin "2") (pinfunction "2_2") (pintype "passive"))
      (node (ref "C50") (pin "2") (pinfunction "2_2") (pintype "passive"))
      (node (ref "C51") (pin "2") (pinfunction "2_2") (pintype "passive"))
      (node (ref "C52") (pin "2") (pinfunction "2_2") (pintype "passive"))
      (node (ref "C53") (pin "2") (pinfunction "2_2") (pintype "passive"))
      (node (ref "C6") (pin "2") (pinfunction "2_2") (pintype "passive"))
      (node (ref "C7") (pin "2") (pinfunction "2_2") (pintype "passive"))
      (node (ref "C8") (pin "2") (pinfunction "2_2") (pintype "passive"))
      (node (ref "E2") (pin "1") (pinfunction "A_1") (pintype "passive"))
      (node (ref "E5") (pin "1") (pinfunction "A_1") (pintype "passive"))
      (node (ref "E6") (pin "1") (pinfunction "A_1") (pintype "passive"))
      (node (ref "R1") (pin "2") (pinfunction "2_2") (pintype "passive"))
      (node (ref "R11") (pin "2") (pinfunction "2_2") (pintype "passive"))
      (node (ref "R12") (pin "2") (pinfunction "2_2") (pintype "passive"))
      (node (ref "R13") (pin "1") (pinfunction "1_1") (pintype "passive"))
      (node (ref "R14") (pin "1") (pinfunction "1_1") (pintype "passive"))
      (node (ref "R17") (pin "2") (pinfunction "2_2") (pintype "passive"))
      (node (ref "R18") (pin "2") (pinfunction "2_2") (pintype "passive"))
      (node (ref "R30") (pin "2") (pinfunction "2_2") (pintype "passive"))
      (node (ref "R5") (pin "2") (pinfunction "2_2") (pintype "passive"))
      (node (ref "R6") (pin "2") (pinfunction "2_2") (pintype "passive"))
      (node (ref "R7") (pin "2") (pinfunction "2_2") (pintype "passive"))
      (node (ref "R9") (pin "2") (pinfunction "2_2") (pintype "passive"))
      (node (ref "SWD1") (pin "1") (pinfunction "1_1") (pintype "passive"))
      (node (ref "U1") (pin "1") (pinfunction "VDD_1") (pintype "passive"))
      (node (ref "U1") (pin "24") (pinfunction "VDD_24") (pintype "passive"))
      (node (ref "U1") (pin "48") (pinfunction "VDD_48") (pintype "passive"))
      (node (ref "U1") (pin "9") (pinfunction "VDDA_9") (pintype "passive"))
      (node (ref "U3") (pin "2") (pinfunction "O_2") (pintype "passive"))
      (node (ref "U5") (pin "5") (pinfunction "VCC_5") (pintype "passive"))
      (node (ref "U6") (pin "5") (pinfunction "VCC_5") (pintype "passive"))
      (node (ref "U7") (pin "5") (pinfunction "VCC_5") (pintype "passive"))
      (node (ref "UART") (pin "1") (pinfunction "1_1") (pintype "passive"))
    )
    (net (code "65") (name "5V") (class "Default")
      (node (ref "B1") (pin "1") (pinfunction "1_1") (pintype "passive"))
      (node (ref "C1") (pin "2") (pinfunction "2_2") (pintype "passive"))
      (node (ref "C10") (pin "2") (pinfunction "2_2") (pintype "passive"))
      (node (ref "C11") (pin "2") (pinfunction "2_2") (pintype "passive"))
      (node (ref "C12") (pin "2") (pinfunction "2_2") (pintype "passive"))
      (node (ref "C13") (pin "2") (pinfunction "2_2") (pintype "passive"))
      (node (ref "C15") (pin "2") (pinfunction "2_2") (pintype "passive"))
      (node (ref "C19") (pin "2") (pinfunction "2_2") (pintype "passive"))
      (node (ref "C2") (pin "2") (pinfunction "2_2") (pintype "passive"))
      (node (ref "C20") (pin "2") (pinfunction "2_2") (pintype "passive"))
      (node (ref "C21") (pin "2") (pinfunction "2_2") (pintype "passive"))
      (node (ref "C22") (pin "2") (pinfunction "2_2") (pintype "passive"))
      (node (ref "C23") (pin "2") (pinfunction "2_2") (pintype "passive"))
      (node (ref "C24") (pin "2") (pinfunction "2_2") (pintype "passive"))
      (node (ref "C25") (pin "2") (pinfunction "2_2") (pintype "passive"))
      (node (ref "C26") (pin "2") (pinfunction "2_2") (pintype "passive"))
      (node (ref "C29") (pin "2") (pinfunction "2_2") (pintype "passive"))
      (node (ref "C3") (pin "2") (pinfunction "2_2") (pintype "passive"))
      (node (ref "C30") (pin "2") (pinfunction "2_2") (pintype "passive"))
      (node (ref "C31") (pin "2") (pinfunction "2_2") (pintype "passive"))
      (node (ref "C32") (pin "2") (pinfunction "2_2") (pintype "passive"))
      (node (ref "C33") (pin "2") (pinfunction "2_2") (pintype "passive"))
      (node (ref "C34") (pin "2") (pinfunction "2_2") (pintype "passive"))
      (node (ref "C37") (pin "2") (pinfunction "2_2") (pintype "passive"))
      (node (ref "C38") (pin "2") (pinfunction "2_2") (pintype "passive"))
      (node (ref "C39") (pin "2") (pinfunction "2_2") (pintype "passive"))
      (node (ref "C40") (pin "2") (pinfunction "2_2") (pintype "passive"))
      (node (ref "C41") (pin "2") (pinfunction "2_2") (pintype "passive"))
      (node (ref "C42") (pin "2") (pinfunction "2_2") (pintype "passive"))
      (node (ref "C43") (pin "2") (pinfunction "2_2") (pintype "passive"))
      (node (ref "C44") (pin "2") (pinfunction "2_2") (pintype "passive"))
      (node (ref "E3") (pin "1") (pinfunction "A_1") (pintype "passive"))
      (node (ref "E4") (pin "1") (pinfunction "A_1") (pintype "passive"))
      (node (ref "GRB1") (pin "1") (pinfunction "VDD_1") (pintype "passive"))
      (node (ref "GRB10") (pin "1") (pinfunction "VDD_1") (pintype "passive"))
      (node (ref "GRB11") (pin "1") (pinfunction "VDD_1") (pintype "passive"))
      (node (ref "GRB12") (pin "1") (pinfunction "VDD_1") (pintype "passive"))
      (node (ref "GRB13") (pin "1") (pinfunction "VDD_1") (pintype "passive"))
      (node (ref "GRB14") (pin "1") (pinfunction "VDD_1") (pintype "passive"))
      (node (ref "GRB15") (pin "1") (pinfunction "VDD_1") (pintype "passive"))
      (node (ref "GRB16") (pin "1") (pinfunction "VDD_1") (pintype "passive"))
      (node (ref "GRB17") (pin "1") (pinfunction "VDD_1") (pintype "passive"))
      (node (ref "GRB18") (pin "1") (pinfunction "VDD_1") (pintype "passive"))
      (node (ref "GRB19") (pin "1") (pinfunction "VDD_1") (pintype "passive"))
      (node (ref "GRB2") (pin "1") (pinfunction "VDD_1") (pintype "passive"))
      (node (ref "GRB20") (pin "1") (pinfunction "VDD_1") (pintype "passive"))
      (node (ref "GRB21") (pin "1") (pinfunction "VDD_1") (pintype "passive"))
      (node (ref "GRB22") (pin "1") (pinfunction "VDD_1") (pintype "passive"))
      (node (ref "GRB23") (pin "1") (pinfunction "VDD_1") (pintype "passive"))
      (node (ref "GRB24") (pin "1") (pinfunction "VDD_1") (pintype "passive"))
      (node (ref "GRB25") (pin "1") (pinfunction "VDD_1") (pintype "passive"))
      (node (ref "GRB26") (pin "1") (pinfunction "VDD_1") (pintype "passive"))
      (node (ref "GRB27") (pin "1") (pinfunction "VDD_1") (pintype "passive"))
      (node (ref "GRB3") (pin "1") (pinfunction "VDD_1") (pintype "passive"))
      (node (ref "GRB4") (pin "1") (pinfunction "VDD_1") (pintype "passive"))
      (node (ref "GRB5") (pin "1") (pinfunction "VDD_1") (pintype "passive"))
      (node (ref "GRB6") (pin "1") (pinfunction "VDD_1") (pintype "passive"))
      (node (ref "GRB7") (pin "1") (pinfunction "VDD_1") (pintype "passive"))
      (node (ref "GRB8") (pin "1") (pinfunction "VDD_1") (pintype "passive"))
      (node (ref "GRB9") (pin "1") (pinfunction "VDD_1") (pintype "passive"))
      (node (ref "L1") (pin "2") (pinfunction "2_2") (pintype "passive"))
      (node (ref "R10") (pin "2") (pinfunction "2_2") (pintype "passive"))
      (node (ref "R2") (pin "2") (pinfunction "2_2") (pintype "passive"))
      (node (ref "R8") (pin "2") (pinfunction "2_2") (pintype "passive"))
      (node (ref "U3") (pin "3") (pinfunction "I_3") (pintype "passive"))
      (node (ref "U4") (pin "10") (pinfunction "VDD_10") (pintype "passive"))
    )
    (net (code "66") (name "12V") (class "Default")
      (node (ref "E1") (pin "1") (pinfunction "A_1") (pintype "passive"))
      (node (ref "E7") (pin "1") (pinfunction "A_1") (pintype "passive"))
      (node (ref "Q6") (pin "3") (pinfunction "S_3") (pintype "passive"))
      (node (ref "R28") (pin "2") (pinfunction "2_2") (pintype "passive"))
      (node (ref "R3") (pin "1") (pinfunction "1_1") (pintype "passive"))
      (node (ref "U2") (pin "5") (pinfunction "IN_5") (pintype "passive"))
      (node (ref "VD1") (pin "2") (pinfunction "K_2") (pintype "passive"))
    )
    (net (code "67") (name "ETX_12V") (class "Default")
      (node (ref "CON1") (pin "1") (pintype "power_in"))
      (node (ref "VD1") (pin "1") (pinfunction "A_1") (pintype "passive"))
    )
    (net (code "68") (name "GND") (class "Default")
      (node (ref "C1") (pin "1") (pinfunction "1_1") (pintype "passive"))
      (node (ref "C10") (pin "1") (pinfunction "1_1") (pintype "passive"))
      (node (ref "C11") (pin "1") (pinfunction "1_1") (pintype "passive"))
      (node (ref "C12") (pin "1") (pinfunction "1_1") (pintype "passive"))
      (node (ref "C13") (pin "1") (pinfunction "1_1") (pintype "passive"))
      (node (ref "C14") (pin "1") (pinfunction "1_1") (pintype "passive"))
      (node (ref "C15") (pin "1") (pinfunction "1_1") (pintype "passive"))
      (node (ref "C16") (pin "1") (pinfunction "1_1") (pintype "passive"))
      (node (ref "C17") (pin "1") (pinfunction "1_1") (pintype "passive"))
      (node (ref "C18") (pin "1") (pinfunction "1_1") (pintype "passive"))
      (node (ref "C19") (pin "1") (pinfunction "1_1") (pintype "passive"))
      (node (ref "C2") (pin "1") (pinfunction "1_1") (pintype "passive"))
      (node (ref "C20") (pin "1") (pinfunction "1_1") (pintype "passive"))
      (node (ref "C21") (pin "1") (pinfunction "1_1") (pintype "passive"))
      (node (ref "C22") (pin "1") (pinfunction "1_1") (pintype "passive"))
      (node (ref "C23") (pin "1") (pinfunction "1_1") (pintype "passive"))
      (node (ref "C24") (pin "1") (pinfunction "1_1") (pintype "passive"))
      (node (ref "C25") (pin "1") (pinfunction "1_1") (pintype "passive"))
      (node (ref "C26") (pin "1") (pinfunction "1_1") (pintype "passive"))
      (node (ref "C27") (pin "1") (pinfunction "1_1") (pintype "passive"))
      (node (ref "C28") (pin "1") (pinfunction "1_1") (pintype "passive"))
      (node (ref "C29") (pin "1") (pinfunction "1_1") (pintype "passive"))
      (node (ref "C3") (pin "1") (pinfunction "1_1") (pintype "passive"))
      (node (ref "C30") (pin "1") (pinfunction "1_1") (pintype "passive"))
      (node (ref "C31") (pin "1") (pinfunction "1_1") (pintype "passive"))
      (node (ref "C32") (pin "1") (pinfunction "1_1") (pintype "passive"))
      (node (ref "C33") (pin "1") (pinfunction "1_1") (pintype "passive"))
      (node (ref "C34") (pin "1") (pinfunction "1_1") (pintype "passive"))
      (node (ref "C35") (pin "2") (pinfunction "2_2") (pintype "passive"))
      (node (ref "C36") (pin "2") (pinfunction "2_2") (pintype "passive"))
      (node (ref "C37") (pin "1") (pinfunction "1_1") (pintype "passive"))
      (node (ref "C38") (pin "1") (pinfunction "1_1") (pintype "passive"))
      (node (ref "C39") (pin "1") (pinfunction "1_1") (pintype "passive"))
      (node (ref "C40") (pin "1") (pinfunction "1_1") (pintype "passive"))
      (node (ref "C41") (pin "1") (pinfunction "1_1") (pintype "passive"))
      (node (ref "C42") (pin "1") (pinfunction "1_1") (pintype "passive"))
      (node (ref "C43") (pin "1") (pinfunction "1_1") (pintype "passive"))
      (node (ref "C44") (pin "1") (pinfunction "1_1") (pintype "passive"))
      (node (ref "C45") (pin "2") (pinfunction "2_2") (pintype "passive"))
      (node (ref "C46") (pin "2") (pinfunction "2_2") (pintype "passive"))
      (node (ref "C47") (pin "2") (pinfunction "2_2") (pintype "passive"))
      (node (ref "C48") (pin "1") (pinfunction "1_1") (pintype "passive"))
      (node (ref "C49") (pin "1") (pinfunction "1_1") (pintype "passive"))
      (node (ref "C5") (pin "1") (pinfunction "1_1") (pintype "passive"))
      (node (ref "C50") (pin "1") (pinfunction "1_1") (pintype "passive"))
      (node (ref "C51") (pin "1") (pinfunction "1_1") (pintype "passive"))
      (node (ref "C52") (pin "1") (pinfunction "1_1") (pintype "passive"))
      (node (ref "C53") (pin "1") (pinfunction "1_1") (pintype "passive"))
      (node (ref "C6") (pin "1") (pinfunction "1_1") (pintype "passive"))
      (node (ref "C7") (pin "1") (pinfunction "1_1") (pintype "passive"))
      (node (ref "C8") (pin "1") (pinfunction "1_1") (pintype "passive"))
      (node (ref "C9") (pin "1") (pinfunction "1_1") (pintype "passive"))
      (node (ref "CON1") (pin "2") (pintype "power_in"))
      (node (ref "E1") (pin "2") (pinfunction "K_2") (pintype "passive"))
      (node (ref "E2") (pin "2") (pinfunction "K_2") (pintype "passive"))
      (node (ref "E3") (pin "2") (pinfunction "K_2") (pintype "passive"))
      (node (ref "E4") (pin "2") (pinfunction "K_2") (pintype "passive"))
      (node (ref "E5") (pin "2") (pinfunction "K_2") (pintype "passive"))
      (node (ref "E6") (pin "2") (pinfunction "K_2") (pintype "passive"))
      (node (ref "E7") (pin "2") (pinfunction "K_2") (pintype "passive"))
      (node (ref "GRB1") (pin "3") (pinfunction "GND_3") (pintype "passive"))
      (node (ref "GRB10") (pin "3") (pinfunction "GND_3") (pintype "passive"))
      (node (ref "GRB11") (pin "3") (pinfunction "GND_3") (pintype "passive"))
      (node (ref "GRB12") (pin "3") (pinfunction "GND_3") (pintype "passive"))
      (node (ref "GRB13") (pin "3") (pinfunction "GND_3") (pintype "passive"))
      (node (ref "GRB14") (pin "3") (pinfunction "GND_3") (pintype "passive"))
      (node (ref "GRB15") (pin "3") (pinfunction "GND_3") (pintype "passive"))
      (node (ref "GRB16") (pin "3") (pinfunction "GND_3") (pintype "passive"))
      (node (ref "GRB17") (pin "3") (pinfunction "GND_3") (pintype "passive"))
      (node (ref "GRB18") (pin "3") (pinfunction "GND_3") (pintype "passive"))
      (node (ref "GRB19") (pin "3") (pinfunction "GND_3") (pintype "passive"))
      (node (ref "GRB2") (pin "3") (pinfunction "GND_3") (pintype "passive"))
      (node (ref "GRB20") (pin "3") (pinfunction "GND_3") (pintype "passive"))
      (node (ref "GRB21") (pin "3") (pinfunction "GND_3") (pintype "passive"))
      (node (ref "GRB22") (pin "3") (pinfunction "GND_3") (pintype "passive"))
      (node (ref "GRB23") (pin "3") (pinfunction "GND_3") (pintype "passive"))
      (node (ref "GRB24") (pin "3") (pinfunction "GND_3") (pintype "passive"))
      (node (ref "GRB25") (pin "3") (pinfunction "GND_3") (pintype "passive"))
      (node (ref "GRB26") (pin "3") (pinfunction "GND_3") (pintype "passive"))
      (node (ref "GRB27") (pin "3") (pinfunction "GND_3") (pintype "passive"))
      (node (ref "GRB3") (pin "3") (pinfunction "GND_3") (pintype "passive"))
      (node (ref "GRB4") (pin "3") (pinfunction "GND_3") (pintype "passive"))
      (node (ref "GRB5") (pin "3") (pinfunction "GND_3") (pintype "passive"))
      (node (ref "GRB6") (pin "3") (pinfunction "GND_3") (pintype "passive"))
      (node (ref "GRB7") (pin "3") (pinfunction "GND_3") (pintype "passive"))
      (node (ref "GRB8") (pin "3") (pinfunction "GND_3") (pintype "passive"))
      (node (ref "GRB9") (pin "3") (pinfunction "GND_3") (pintype "passive"))
      (node (ref "JP1") (pin "4") (pinfunction "4_4") (pintype "passive"))
      (node (ref "Q3") (pin "2") (pinfunction "e_2") (pintype "passive"))
      (node (ref "Q4") (pin "2") (pinfunction "e_2") (pintype "passive"))
      (node (ref "Q5") (pin "2") (pinfunction "e_2") (pintype "passive"))
      (node (ref "Q7") (pin "2") (pinfunction "e_2") (pintype "passive"))
      (node (ref "R22") (pin "1") (pinfunction "1_1") (pintype "passive"))
      (node (ref "R23") (pin "1") (pinfunction "1_1") (pintype "passive"))
      (node (ref "R24") (pin "1") (pinfunction "1_1") (pintype "passive"))
      (node (ref "R4") (pin "1") (pinfunction "1_1") (pintype "passive"))
      (node (ref "REC1") (pin "2") (pinfunction "GND_2") (pintype "passive"))
      (node (ref "REC2") (pin "2") (pinfunction "GND_2") (pintype "passive"))
      (node (ref "SWD1") (pin "2") (pinfunction "2_2") (pintype "passive"))
      (node (ref "U1") (pin "23") (pinfunction "VSS_23") (pintype "passive"))
      (node (ref "U1") (pin "44") (pinfunction "BOOT0_44") (pintype "passive"))
      (node (ref "U1") (pin "47") (pinfunction "VSS_47") (pintype "passive"))
      (node (ref "U1") (pin "8") (pinfunction "VSSA_8") (pintype "passive"))
      (node (ref "U2") (pin "2") (pinfunction "GND_2") (pintype "passive"))
      (node (ref "U3") (pin "1") (pinfunction "G_1") (pintype "passive"))
      (node (ref "U4") (pin "4") (pinfunction "GND_4") (pintype "passive"))
      (node (ref "U5") (pin "2") (pinfunction "GND_2") (pintype "passive"))
      (node (ref "U6") (pin "2") (pinfunction "GND_2") (pintype "passive"))
      (node (ref "U7") (pin "2") (pinfunction "GND_2") (pintype "passive"))
      (node (ref "UART") (pin "2") (pinfunction "2_2") (pintype "passive"))
      (node (ref "VD2") (pin "1") (pinfunction "A_1") (pintype "passive"))
    )
    (net (code "69") (name "Net-(D1-A)") (class "Default")
      (node (ref "D1") (pin "1") (pinfunction "A_1") (pintype "passive"))
      (node (ref "R13") (pin "2") (pinfunction "2_2") (pintype "passive"))
    )
    (net (code "70") (name "Net-(D1-K)") (class "Default")
      (node (ref "D1") (pin "2") (pinfunction "K_2") (pintype "passive"))
      (node (ref "Q4") (pin "3") (pinfunction "c_3") (pintype "passive"))
    )
    (net (code "71") (name "Net-(D2-A)") (class "Default")
      (node (ref "D2") (pin "1") (pinfunction "A_1") (pintype "passive"))
      (node (ref "R14") (pin "2") (pinfunction "2_2") (pintype "passive"))
    )
    (net (code "72") (name "Net-(D2-K)") (class "Default")
      (node (ref "D2") (pin "2") (pinfunction "K_2") (pintype "passive"))
      (node (ref "Q5") (pin "3") (pinfunction "c_3") (pintype "passive"))
    )
    (net (code "73") (name "Net-(Q1-G)") (class "Default")
      (node (ref "Q1") (pin "1") (pinfunction "G_1") (pintype "passive"))
      (node (ref "R5") (pin "1") (pinfunction "1_1") (pintype "passive"))
    )
    (net (code "74") (name "Net-(Q2-G)") (class "Default")
      (node (ref "Q2") (pin "1") (pinfunction "G_1") (pintype "passive"))
      (node (ref "R6") (pin "1") (pinfunction "1_1") (pintype "passive"))
    )
    (net (code "75") (name "Net-(Q3-b)") (class "Default")
      (node (ref "Q3") (pin "1") (pinfunction "b_1") (pintype "passive"))
      (node (ref "R19") (pin "2") (pinfunction "2_2") (pintype "passive"))
      (node (ref "R22") (pin "2") (pinfunction "2_2") (pintype "passive"))
    )
    (net (code "76") (name "Net-(Q3-c)") (class "Default")
      (node (ref "B1") (pin "2") (pinfunction "2_2") (pintype "passive"))
      (node (ref "Q3") (pin "3") (pinfunction "c_3") (pintype "passive"))
    )
    (net (code "77") (name "Net-(Q4-b)") (class "Default")
      (node (ref "Q4") (pin "1") (pinfunction "b_1") (pintype "passive"))
      (node (ref "R20") (pin "2") (pinfunction "2_2") (pintype "passive"))
      (node (ref "R23") (pin "2") (pinfunction "2_2") (pintype "passive"))
    )
    (net (code "78") (name "Net-(Q5-b)") (class "Default")
      (node (ref "Q5") (pin "1") (pinfunction "b_1") (pintype "passive"))
      (node (ref "R21") (pin "2") (pinfunction "2_2") (pintype "passive"))
      (node (ref "R24") (pin "2") (pinfunction "2_2") (pintype "passive"))
    )
    (net (code "79") (name "Net-(Q6-G)") (class "Default")
      (node (ref "Q6") (pin "1") (pinfunction "G_1") (pintype "passive"))
      (node (ref "R28") (pin "1") (pinfunction "1_1") (pintype "passive"))
      (node (ref "R29") (pin "2") (pinfunction "2_2") (pintype "passive"))
    )
    (net (code "80") (name "Net-(Q7-b)") (class "Default")
      (node (ref "Q7") (pin "1") (pinfunction "b_1") (pintype "passive"))
      (node (ref "R31") (pin "2") (pinfunction "2_2") (pintype "passive"))
    )
    (net (code "81") (name "Net-(Q7-c)") (class "Default")
      (node (ref "Q7") (pin "3") (pinfunction "c_3") (pintype "passive"))
      (node (ref "R29") (pin "1") (pinfunction "1_1") (pintype "passive"))
    )
    (net (code "82") (name "Net-(R25-Pad1)") (class "Default")
      (node (ref "R25") (pin "1") (pinfunction "1_1") (pintype "passive"))
      (node (ref "T1") (pin "1") (pintype "passive"))
    )
    (net (code "83") (name "Net-(R26-Pad1)") (class "Default")
      (node (ref "R26") (pin "1") (pinfunction "1_1") (pintype "passive"))
      (node (ref "T2") (pin "1") (pintype "passive"))
    )
    (net (code "84") (name "Net-(R27-Pad1)") (class "Default")
      (node (ref "R27") (pin "1") (pinfunction "1_1") (pintype "passive"))
      (node (ref "T3") (pin "1") (pintype "passive"))
    )
    (net (code "85") (name "Net-(REC1-OUT)") (class "Default")
      (node (ref "R11") (pin "1") (pinfunction "1_1") (pintype "passive"))
      (node (ref "R15") (pin "1") (pinfunction "1_1") (pintype "passive"))
      (node (ref "REC1") (pin "1") (pinfunction "OUT_1") (pintype "passive"))
    )
    (net (code "86") (name "Net-(REC1-VCC)") (class "Default")
      (node (ref "R17") (pin "1") (pinfunction "1_1") (pintype "passive"))
      (node (ref "REC1") (pin "3") (pinfunction "VCC_3") (pintype "passive"))
    )
    (net (code "87") (name "Net-(REC2-OUT)") (class "Default")
      (node (ref "R12") (pin "1") (pinfunction "1_1") (pintype "passive"))
      (node (ref "R16") (pin "1") (pinfunction "1_1") (pintype "passive"))
      (node (ref "REC2") (pin "1") (pinfunction "OUT_1") (pintype "passive"))
    )
    (net (code "88") (name "Net-(REC2-VCC)") (class "Default")
      (node (ref "R18") (pin "1") (pinfunction "1_1") (pintype "passive"))
      (node (ref "REC2") (pin "3") (pinfunction "VCC_3") (pintype "passive"))
    )
    (net (code "89") (name "Net-(U2-BS)") (class "Default")
      (node (ref "C4") (pin "1") (pinfunction "1_1") (pintype "passive"))
      (node (ref "U2") (pin "1") (pinfunction "BS_1") (pintype "passive"))
    )
    (net (code "90") (name "Net-(U2-EN)") (class "Default")
      (node (ref "R3") (pin "2") (pinfunction "2_2") (pintype "passive"))
      (node (ref "U2") (pin "4") (pinfunction "EN_4") (pintype "passive"))
    )
    (net (code "91") (name "Net-(U2-FB)") (class "Default")
      (node (ref "R2") (pin "1") (pinfunction "1_1") (pintype "passive"))
      (node (ref "R4") (pin "2") (pinfunction "2_2") (pintype "passive"))
      (node (ref "U2") (pin "3") (pinfunction "FB_3") (pintype "passive"))
    )
    (net (code "92") (name "Net-(U2-SW)") (class "Default")
      (node (ref "C4") (pin "2") (pinfunction "2_2") (pintype "passive"))
      (node (ref "L1") (pin "1") (pinfunction "1_1") (pintype "passive"))
      (node (ref "U2") (pin "6") (pinfunction "SW_6") (pintype "passive"))
    )
    (net (code "93") (name "Net-(U5-KEY)") (class "Default")
      (node (ref "R25") (pin "2") (pinfunction "2_2") (pintype "passive"))
      (node (ref "U5") (pin "3") (pinfunction "KEY_3") (pintype "passive"))
    )
    (net (code "94") (name "Net-(U5-TOG)") (class "Default")
      (node (ref "C45") (pin "1") (pinfunction "1_1") (pintype "passive"))
      (node (ref "U5") (pin "6") (pinfunction "TOG_6") (pintype "passive"))
    )
    (net (code "95") (name "Net-(U6-KEY)") (class "Default")
      (node (ref "R26") (pin "2") (pinfunction "2_2") (pintype "passive"))
      (node (ref "U6") (pin "3") (pinfunction "KEY_3") (pintype "passive"))
    )
    (net (code "96") (name "Net-(U6-TOG)") (class "Default")
      (node (ref "C46") (pin "1") (pinfunction "1_1") (pintype "passive"))
      (node (ref "U6") (pin "6") (pinfunction "TOG_6") (pintype "passive"))
    )
    (net (code "97") (name "Net-(U7-KEY)") (class "Default")
      (node (ref "R27") (pin "2") (pinfunction "2_2") (pintype "passive"))
      (node (ref "U7") (pin "3") (pinfunction "KEY_3") (pintype "passive"))
    )
    (net (code "98") (name "Net-(U7-TOG)") (class "Default")
      (node (ref "C47") (pin "1") (pinfunction "1_1") (pintype "passive"))
      (node (ref "U7") (pin "6") (pinfunction "TOG_6") (pintype "passive"))
    )
    (net (code "99") (name "unconnected-(CON1-Pad3)") (class "Default")
      (node (ref "CON1") (pin "3") (pintype "power_in+no_connect"))
    )
    (net (code "100") (name "unconnected-(GRB3-DOUT-Pad2)") (class "Default")
      (node (ref "GRB3") (pin "2") (pinfunction "DOUT_2") (pintype "passive"))
    )
    (net (code "101") (name "unconnected-(GRB27-DOUT-Pad2)") (class "Default")
      (node (ref "GRB27") (pin "2") (pinfunction "DOUT_2") (pintype "passive"))
    )
    (net (code "102") (name "unconnected-(U1A-PA0-Pad10)") (class "Default")
      (node (ref "U1") (pin "10") (pinfunction "PA0_10") (pintype "passive"))
    )
    (net (code "103") (name "unconnected-(U1A-PA1-Pad11)") (class "Default")
      (node (ref "U1") (pin "11") (pinfunction "PA1_11") (pintype "passive"))
    )
    (net (code "104") (name "unconnected-(U1A-PB0-Pad18)") (class "Default")
      (node (ref "U1") (pin "18") (pinfunction "PB0_18") (pintype "passive"))
    )
    (net (code "105") (name "unconnected-(U1A-PB1-Pad19)") (class "Default")
      (node (ref "U1") (pin "19") (pinfunction "PB1_19") (pintype "passive"))
    )
    (net (code "106") (name "unconnected-(U1A-PB2-Pad20)") (class "Default")
      (node (ref "U1") (pin "20") (pinfunction "PB2_20") (pintype "passive"))
    )
    (net (code "107") (name "unconnected-(U1A-PB5-Pad41)") (class "Default")
      (node (ref "U1") (pin "41") (pinfunction "PB5_41") (pintype "passive"))
    )
    (net (code "108") (name "unconnected-(U1A-PB6-Pad42)") (class "Default")
      (node (ref "U1") (pin "42") (pinfunction "PB6_42") (pintype "passive"))
    )
    (net (code "109") (name "unconnected-(U1A-PB7-Pad43)") (class "Default")
      (node (ref "U1") (pin "43") (pinfunction "PB7_43") (pintype "passive"))
    )
    (net (code "110") (name "unconnected-(U1A-PB10-Pad21)") (class "Default")
      (node (ref "U1") (pin "21") (pinfunction "PB10_21") (pintype "passive"))
    )
    (net (code "111") (name "unconnected-(U1A-PB11-Pad22)") (class "Default")
      (node (ref "U1") (pin "22") (pinfunction "PB11_22") (pintype "passive"))
    )
    (net (code "112") (name "unconnected-(U1A-PB13-Pad26)") (class "Default")
      (node (ref "U1") (pin "26") (pinfunction "PB13_26") (pintype "passive"))
    )
    (net (code "113") (name "unconnected-(U1A-PB15-Pad28)") (class "Default")
      (node (ref "U1") (pin "28") (pinfunction "PB15_28") (pintype "passive"))
    )
    (net (code "114") (name "unconnected-(U1A-PC13-Pad2)") (class "Default")
      (node (ref "U1") (pin "2") (pinfunction "PC13_2") (pintype "passive"))
    )
    (net (code "115") (name "unconnected-(U1A-PC14-OSC32_IN(PC14)-Pad3)") (class "Default")
      (node (ref "U1") (pin "3") (pinfunction "PC14-OSC32_IN(PC14)_3") (pintype "passive"))
    )
    (net (code "116") (name "unconnected-(U1A-PC15-OSC32_OUT(PC15)-Pad4)") (class "Default")
      (node (ref "U1") (pin "4") (pinfunction "PC15-OSC32_OUT(PC15)_4") (pintype "passive"))
    )
    (net (code "117") (name "unconnected-(U1A-PF6-Pad35)") (class "Default")
      (node (ref "U1") (pin "35") (pinfunction "PF6_35") (pintype "passive"))
    )
    (net (code "118") (name "unconnected-(U1A-PF7-Pad36)") (class "Default")
      (node (ref "U1") (pin "36") (pinfunction "PF7_36") (pintype "passive"))
    )
    (net (code "119") (name "unconnected-(U5-AHLB-Pad4)") (class "Default")
      (node (ref "U5") (pin "4") (pinfunction "AHLB_4") (pintype "passive"))
    )
    (net (code "120") (name "unconnected-(U6-AHLB-Pad4)") (class "Default")
      (node (ref "U6") (pin "4") (pinfunction "AHLB_4") (pintype "passive"))
    )
    (net (code "121") (name "unconnected-(U7-AHLB-Pad4)") (class "Default")
      (node (ref "U7") (pin "4") (pinfunction "AHLB_4") (pintype "passive"))
    )
  )
)
